# ttl-nixie-clock-generator.net
KiCad netlist of a schematic drawn in EAGLE
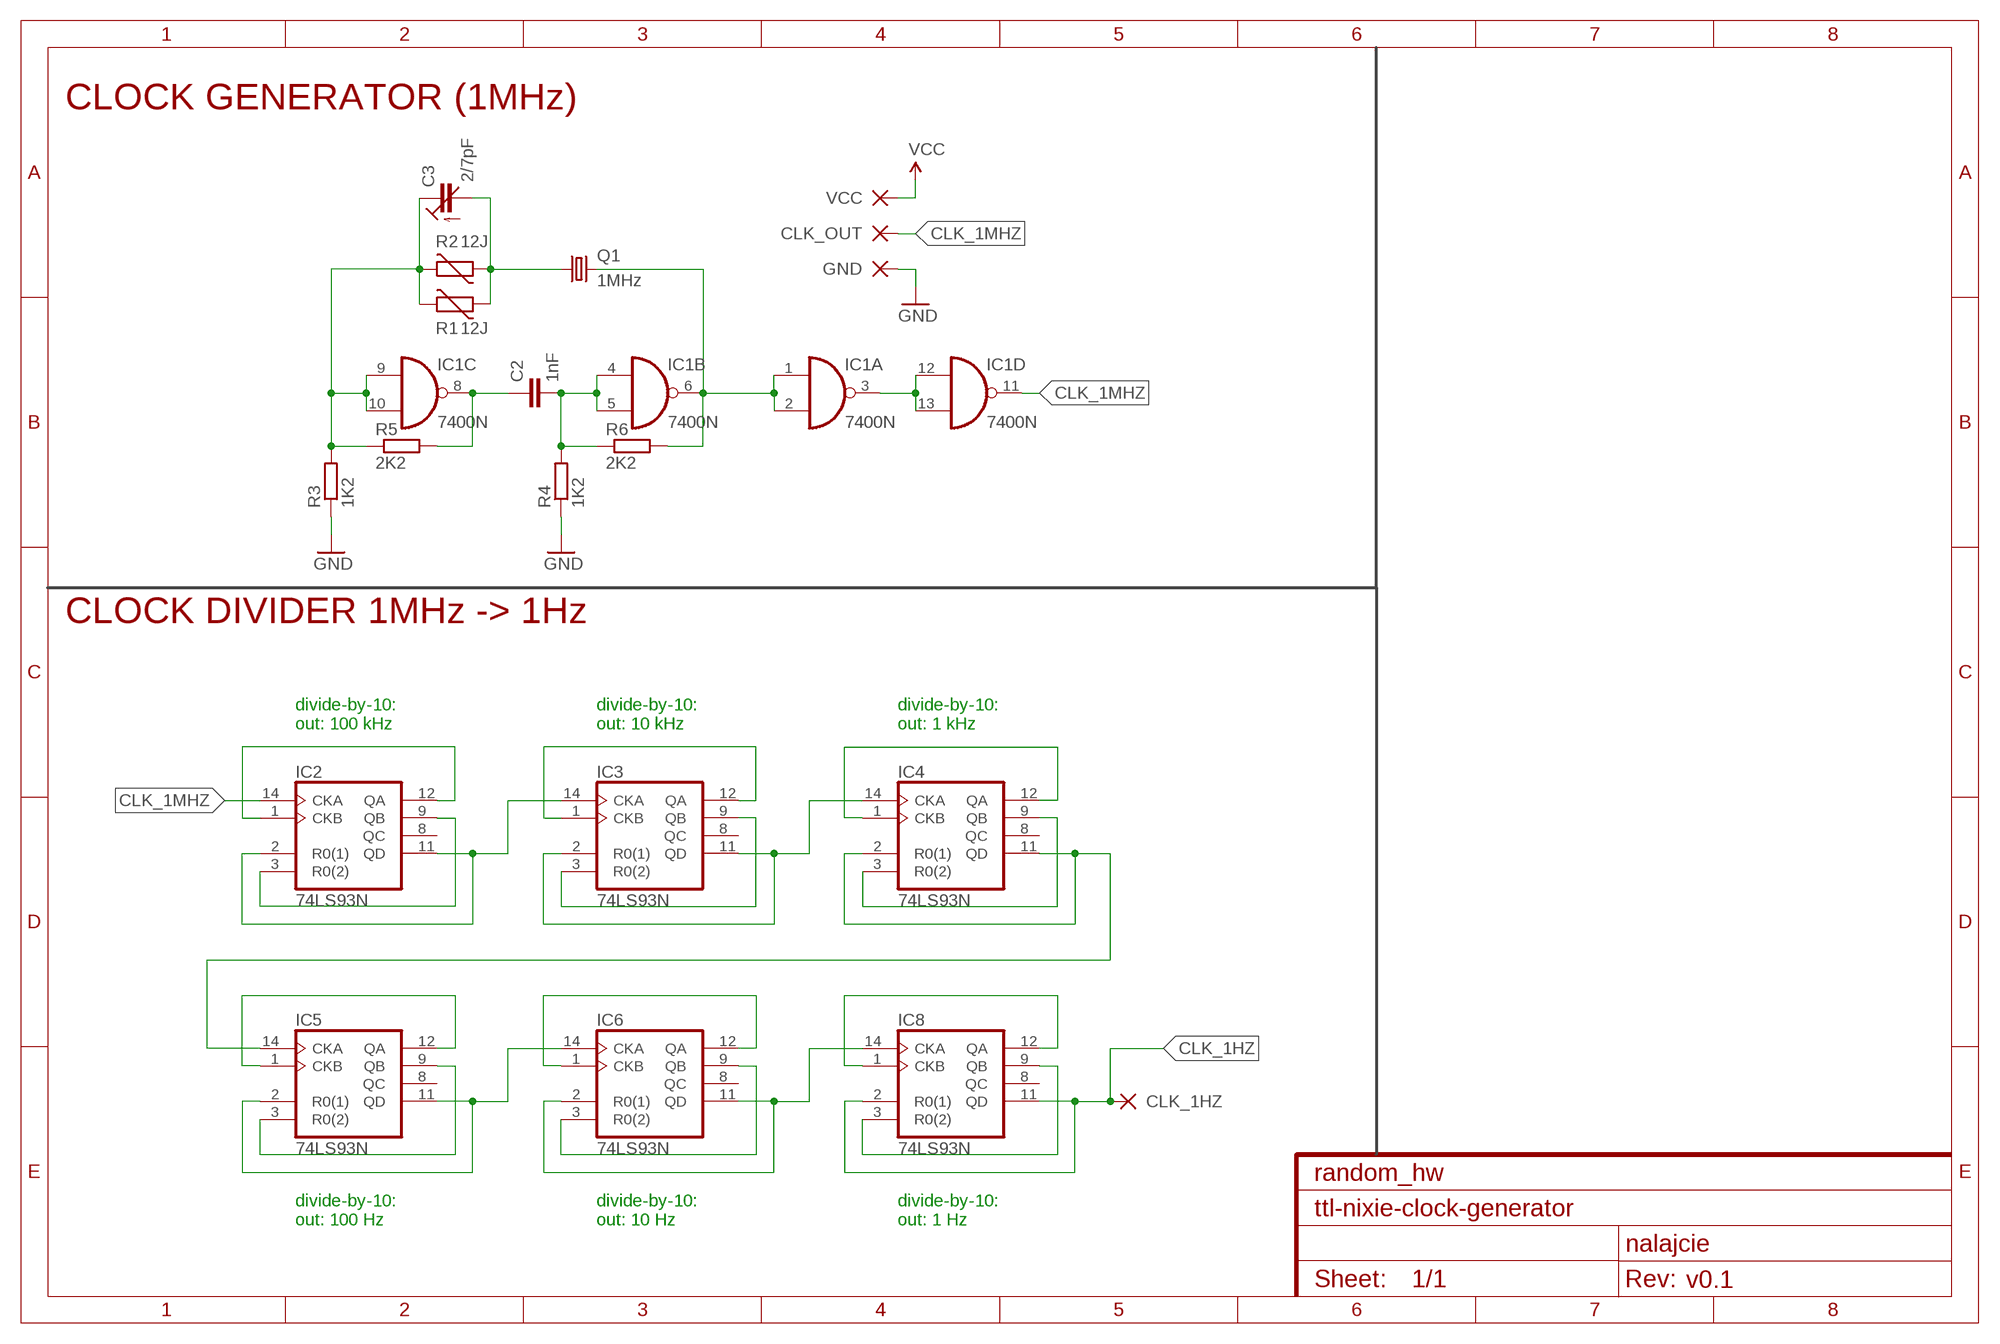
[diagram p0: schematic, sheet 1]

(export (version "E")
  (design (tool "Eeschema 10.0.6"))
  (components
    (comp (ref "C2")
      (value "1nF")
      (footprint "eagle-import:C15B5")
      (libsource (lib "eagle-import") (part "C15/5"))
    )
    (comp (ref "C3")
      (value "2/7pF")
      (footprint "eagle-import:CTRIM808-BC7.5")
      (libsource (lib "eagle-import") (part "C-TRIMM808-7.5"))
    )
    (comp (ref "CLK_1HZ")
      (value "VCC")
      (footprint "eagle-import:2,15_1,0")
      (libsource (lib "eagle-import") (part "2,15/1,0"))
    )
    (comp (ref "CLK_OUT")
      (value "CLK_OUT")
      (footprint "eagle-import:2,15_1,0")
      (libsource (lib "eagle-import") (part "2,15/1,0"))
    )
    (comp (ref "GND")
      (value "GND")
      (footprint "eagle-import:2,15_1,0")
      (libsource (lib "eagle-import") (part "2,15/1,0"))
    )
    (comp (ref "IC1")
      (value "7400N")
      (footprint "eagle-import:DIL14")
      (libsource (lib "eagle-import") (part "7400N"))
    )
    (comp (ref "IC2")
      (value "74LS93N")
      (footprint "eagle-import:DIL14")
      (libsource (lib "eagle-import") (part "7493NLS"))
    )
    (comp (ref "IC3")
      (value "74LS93N")
      (footprint "eagle-import:DIL14")
      (libsource (lib "eagle-import") (part "7493NLS"))
    )
    (comp (ref "IC4")
      (value "74LS93N")
      (footprint "eagle-import:DIL14")
      (libsource (lib "eagle-import") (part "7493NLS"))
    )
    (comp (ref "IC5")
      (value "74LS93N")
      (footprint "eagle-import:DIL14")
      (libsource (lib "eagle-import") (part "7493NLS"))
    )
    (comp (ref "IC6")
      (value "74LS93N")
      (footprint "eagle-import:DIL14")
      (libsource (lib "eagle-import") (part "7493NLS"))
    )
    (comp (ref "IC8")
      (value "74LS93N")
      (footprint "eagle-import:DIL14")
      (libsource (lib "eagle-import") (part "7493NLS"))
    )
    (comp (ref "Q1")
      (value "1MHz")
      (footprint "eagle-import:HC33U-V")
      (libsource (lib "eagle-import") (part "CRYSTALHC33U-V"))
    )
    (comp (ref "R1")
      (value "12J")
      (footprint "eagle-import:R-7,5")
      (libsource (lib "eagle-import") (part "VARISTOR-7,5"))
    )
    (comp (ref "R2")
      (value "12J")
      (footprint "eagle-import:R-7,5")
      (libsource (lib "eagle-import") (part "VARISTOR-7,5"))
    )
    (comp (ref "R3")
      (value "1K2")
      (footprint "eagle-import:0207_12")
      (libsource (lib "eagle-import") (part "R-EU_0207/12"))
    )
    (comp (ref "R4")
      (value "1K2")
      (footprint "eagle-import:0207_12")
      (libsource (lib "eagle-import") (part "R-EU_0207/12"))
    )
    (comp (ref "R5")
      (value "2K2")
      (footprint "eagle-import:0207_12")
      (libsource (lib "eagle-import") (part "R-EU_0207/12"))
    )
    (comp (ref "R6")
      (value "2K2")
      (footprint "eagle-import:0207_12")
      (libsource (lib "eagle-import") (part "R-EU_0207/12"))
    )
    (comp (ref "VCC")
      (value "VCC")
      (footprint "eagle-import:2,15_1,0")
      (libsource (lib "eagle-import") (part "2,15/1,0"))
    )
  )
  (nets
    (net (code "1") (name "CLK_1HZ") (class "Default")
      (node (ref "CLK_1HZ") (pin "1") (pinfunction "P_1") (pintype "passive"))
      (node (ref "IC8") (pin "11") (pinfunction "QD_11") (pintype "output"))
      (node (ref "IC8") (pin "2") (pinfunction "R0(1)_2") (pintype "input"))
    )
    (net (code "2") (name "CLK_1MHZ") (class "Default")
      (node (ref "CLK_OUT") (pin "1") (pinfunction "P_1") (pintype "passive"))
      (node (ref "IC1") (pin "11") (pinfunction "O_11") (pintype "output"))
      (node (ref "IC2") (pin "14") (pinfunction "CKA_14") (pintype "input"))
    )
    (net (code "3") (name "GND") (class "Default")
      (node (ref "GND") (pin "1") (pinfunction "P_1") (pintype "passive"))
      (node (ref "R3") (pin "1") (pinfunction "1_1") (pintype "passive"))
      (node (ref "R4") (pin "1") (pinfunction "1_1") (pintype "passive"))
    )
    (net (code "4") (name "Net-(C3-A)") (class "Default")
      (node (ref "C3") (pin "2") (pinfunction "A_2") (pintype "passive"))
      (node (ref "Q1") (pin "1") (pinfunction "1_1") (pintype "passive"))
      (node (ref "R1") (pin "1") (pinfunction "1_1") (pintype "passive"))
      (node (ref "R2") (pin "1") (pinfunction "1_1") (pintype "passive"))
    )
    (net (code "5") (name "Net-(C3-E)") (class "Default")
      (node (ref "C3") (pin "1") (pinfunction "E_1") (pintype "passive"))
      (node (ref "IC1") (pin "10") (pinfunction "I1_10") (pintype "input"))
      (node (ref "IC1") (pin "9") (pinfunction "I0_9") (pintype "input"))
      (node (ref "R1") (pin "2") (pinfunction "2_2") (pintype "passive"))
      (node (ref "R2") (pin "2") (pinfunction "2_2") (pintype "passive"))
      (node (ref "R3") (pin "2") (pinfunction "2_2") (pintype "passive"))
      (node (ref "R5") (pin "1") (pinfunction "1_1") (pintype "passive"))
    )
    (net (code "6") (name "Net-(IC1A-I0)") (class "Default")
      (node (ref "IC1") (pin "1") (pinfunction "I0_1") (pintype "input"))
      (node (ref "IC1") (pin "2") (pinfunction "I1_2") (pintype "input"))
      (node (ref "IC1") (pin "6") (pinfunction "O_6") (pintype "output"))
      (node (ref "Q1") (pin "2") (pinfunction "2_2") (pintype "passive"))
      (node (ref "R6") (pin "2") (pinfunction "2_2") (pintype "passive"))
    )
    (net (code "7") (name "Net-(IC1A-O)") (class "Default")
      (node (ref "IC1") (pin "12") (pinfunction "I0_12") (pintype "input"))
      (node (ref "IC1") (pin "13") (pinfunction "I1_13") (pintype "input"))
      (node (ref "IC1") (pin "3") (pinfunction "O_3") (pintype "output"))
    )
    (net (code "8") (name "Net-(IC1B-I0)") (class "Default")
      (node (ref "C2") (pin "2") (pinfunction "2_2") (pintype "passive"))
      (node (ref "IC1") (pin "4") (pinfunction "I0_4") (pintype "input"))
      (node (ref "IC1") (pin "5") (pinfunction "I1_5") (pintype "input"))
      (node (ref "R4") (pin "2") (pinfunction "2_2") (pintype "passive"))
      (node (ref "R6") (pin "1") (pinfunction "1_1") (pintype "passive"))
    )
    (net (code "9") (name "Net-(IC1C-O)") (class "Default")
      (node (ref "C2") (pin "1") (pinfunction "1_1") (pintype "passive"))
      (node (ref "IC1") (pin "8") (pinfunction "O_8") (pintype "output"))
      (node (ref "R5") (pin "2") (pinfunction "2_2") (pintype "passive"))
    )
    (net (code "10") (name "Net-(IC2A-CKB)") (class "Default")
      (node (ref "IC2") (pin "1") (pinfunction "CKB_1") (pintype "input"))
      (node (ref "IC2") (pin "12") (pinfunction "QA_12") (pintype "output"))
    )
    (net (code "11") (name "Net-(IC2A-QB)") (class "Default")
      (node (ref "IC2") (pin "3") (pinfunction "R0(2)_3") (pintype "input"))
      (node (ref "IC2") (pin "9") (pinfunction "QB_9") (pintype "output"))
    )
    (net (code "12") (name "Net-(IC2A-QD)") (class "Default")
      (node (ref "IC2") (pin "11") (pinfunction "QD_11") (pintype "output"))
      (node (ref "IC2") (pin "2") (pinfunction "R0(1)_2") (pintype "input"))
      (node (ref "IC3") (pin "14") (pinfunction "CKA_14") (pintype "input"))
    )
    (net (code "13") (name "Net-(IC3A-CKB)") (class "Default")
      (node (ref "IC3") (pin "1") (pinfunction "CKB_1") (pintype "input"))
      (node (ref "IC3") (pin "12") (pinfunction "QA_12") (pintype "output"))
    )
    (net (code "14") (name "Net-(IC3A-QB)") (class "Default")
      (node (ref "IC3") (pin "3") (pinfunction "R0(2)_3") (pintype "input"))
      (node (ref "IC3") (pin "9") (pinfunction "QB_9") (pintype "output"))
    )
    (net (code "15") (name "Net-(IC3A-QD)") (class "Default")
      (node (ref "IC3") (pin "11") (pinfunction "QD_11") (pintype "output"))
      (node (ref "IC3") (pin "2") (pinfunction "R0(1)_2") (pintype "input"))
      (node (ref "IC4") (pin "14") (pinfunction "CKA_14") (pintype "input"))
    )
    (net (code "16") (name "Net-(IC4A-CKB)") (class "Default")
      (node (ref "IC4") (pin "1") (pinfunction "CKB_1") (pintype "input"))
      (node (ref "IC4") (pin "12") (pinfunction "QA_12") (pintype "output"))
    )
    (net (code "17") (name "Net-(IC4A-QB)") (class "Default")
      (node (ref "IC4") (pin "3") (pinfunction "R0(2)_3") (pintype "input"))
      (node (ref "IC4") (pin "9") (pinfunction "QB_9") (pintype "output"))
    )
    (net (code "18") (name "Net-(IC4A-QD)") (class "Default")
      (node (ref "IC4") (pin "11") (pinfunction "QD_11") (pintype "output"))
      (node (ref "IC4") (pin "2") (pinfunction "R0(1)_2") (pintype "input"))
      (node (ref "IC5") (pin "14") (pinfunction "CKA_14") (pintype "input"))
    )
    (net (code "19") (name "Net-(IC5A-CKB)") (class "Default")
      (node (ref "IC5") (pin "1") (pinfunction "CKB_1") (pintype "input"))
      (node (ref "IC5") (pin "12") (pinfunction "QA_12") (pintype "output"))
    )
    (net (code "20") (name "Net-(IC5A-QB)") (class "Default")
      (node (ref "IC5") (pin "3") (pinfunction "R0(2)_3") (pintype "input"))
      (node (ref "IC5") (pin "9") (pinfunction "QB_9") (pintype "output"))
    )
    (net (code "21") (name "Net-(IC5A-QD)") (class "Default")
      (node (ref "IC5") (pin "11") (pinfunction "QD_11") (pintype "output"))
      (node (ref "IC5") (pin "2") (pinfunction "R0(1)_2") (pintype "input"))
      (node (ref "IC6") (pin "14") (pinfunction "CKA_14") (pintype "input"))
    )
    (net (code "22") (name "Net-(IC6A-CKB)") (class "Default")
      (node (ref "IC6") (pin "1") (pinfunction "CKB_1") (pintype "input"))
      (node (ref "IC6") (pin "12") (pinfunction "QA_12") (pintype "output"))
    )
    (net (code "23") (name "Net-(IC6A-QB)") (class "Default")
      (node (ref "IC6") (pin "3") (pinfunction "R0(2)_3") (pintype "input"))
      (node (ref "IC6") (pin "9") (pinfunction "QB_9") (pintype "output"))
    )
    (net (code "24") (name "Net-(IC6A-QD)") (class "Default")
      (node (ref "IC6") (pin "11") (pinfunction "QD_11") (pintype "output"))
      (node (ref "IC6") (pin "2") (pinfunction "R0(1)_2") (pintype "input"))
      (node (ref "IC8") (pin "14") (pinfunction "CKA_14") (pintype "input"))
    )
    (net (code "25") (name "Net-(IC8A-CKB)") (class "Default")
      (node (ref "IC8") (pin "1") (pinfunction "CKB_1") (pintype "input"))
      (node (ref "IC8") (pin "12") (pinfunction "QA_12") (pintype "output"))
    )
    (net (code "26") (name "Net-(IC8A-QB)") (class "Default")
      (node (ref "IC8") (pin "3") (pinfunction "R0(2)_3") (pintype "input"))
      (node (ref "IC8") (pin "9") (pinfunction "QB_9") (pintype "output"))
    )
    (net (code "27") (name "VCC") (class "Default")
      (node (ref "VCC") (pin "1") (pinfunction "P_1") (pintype "passive"))
    )
    (net (code "28") (name "unconnected-(IC2A-QC-Pad8)") (class "Default")
      (node (ref "IC2") (pin "8") (pinfunction "QC_8") (pintype "output"))
    )
    (net (code "29") (name "unconnected-(IC3A-QC-Pad8)") (class "Default")
      (node (ref "IC3") (pin "8") (pinfunction "QC_8") (pintype "output"))
    )
    (net (code "30") (name "unconnected-(IC4A-QC-Pad8)") (class "Default")
      (node (ref "IC4") (pin "8") (pinfunction "QC_8") (pintype "output"))
    )
    (net (code "31") (name "unconnected-(IC5A-QC-Pad8)") (class "Default")
      (node (ref "IC5") (pin "8") (pinfunction "QC_8") (pintype "output"))
    )
    (net (code "32") (name "unconnected-(IC6A-QC-Pad8)") (class "Default")
      (node (ref "IC6") (pin "8") (pinfunction "QC_8") (pintype "output"))
    )
    (net (code "33") (name "unconnected-(IC8A-QC-Pad8)") (class "Default")
      (node (ref "IC8") (pin "8") (pinfunction "QC_8") (pintype "output"))
    )
  )
)
